# Vayu_i2c.net
KiCad netlist of a schematic drawn in EAGLE
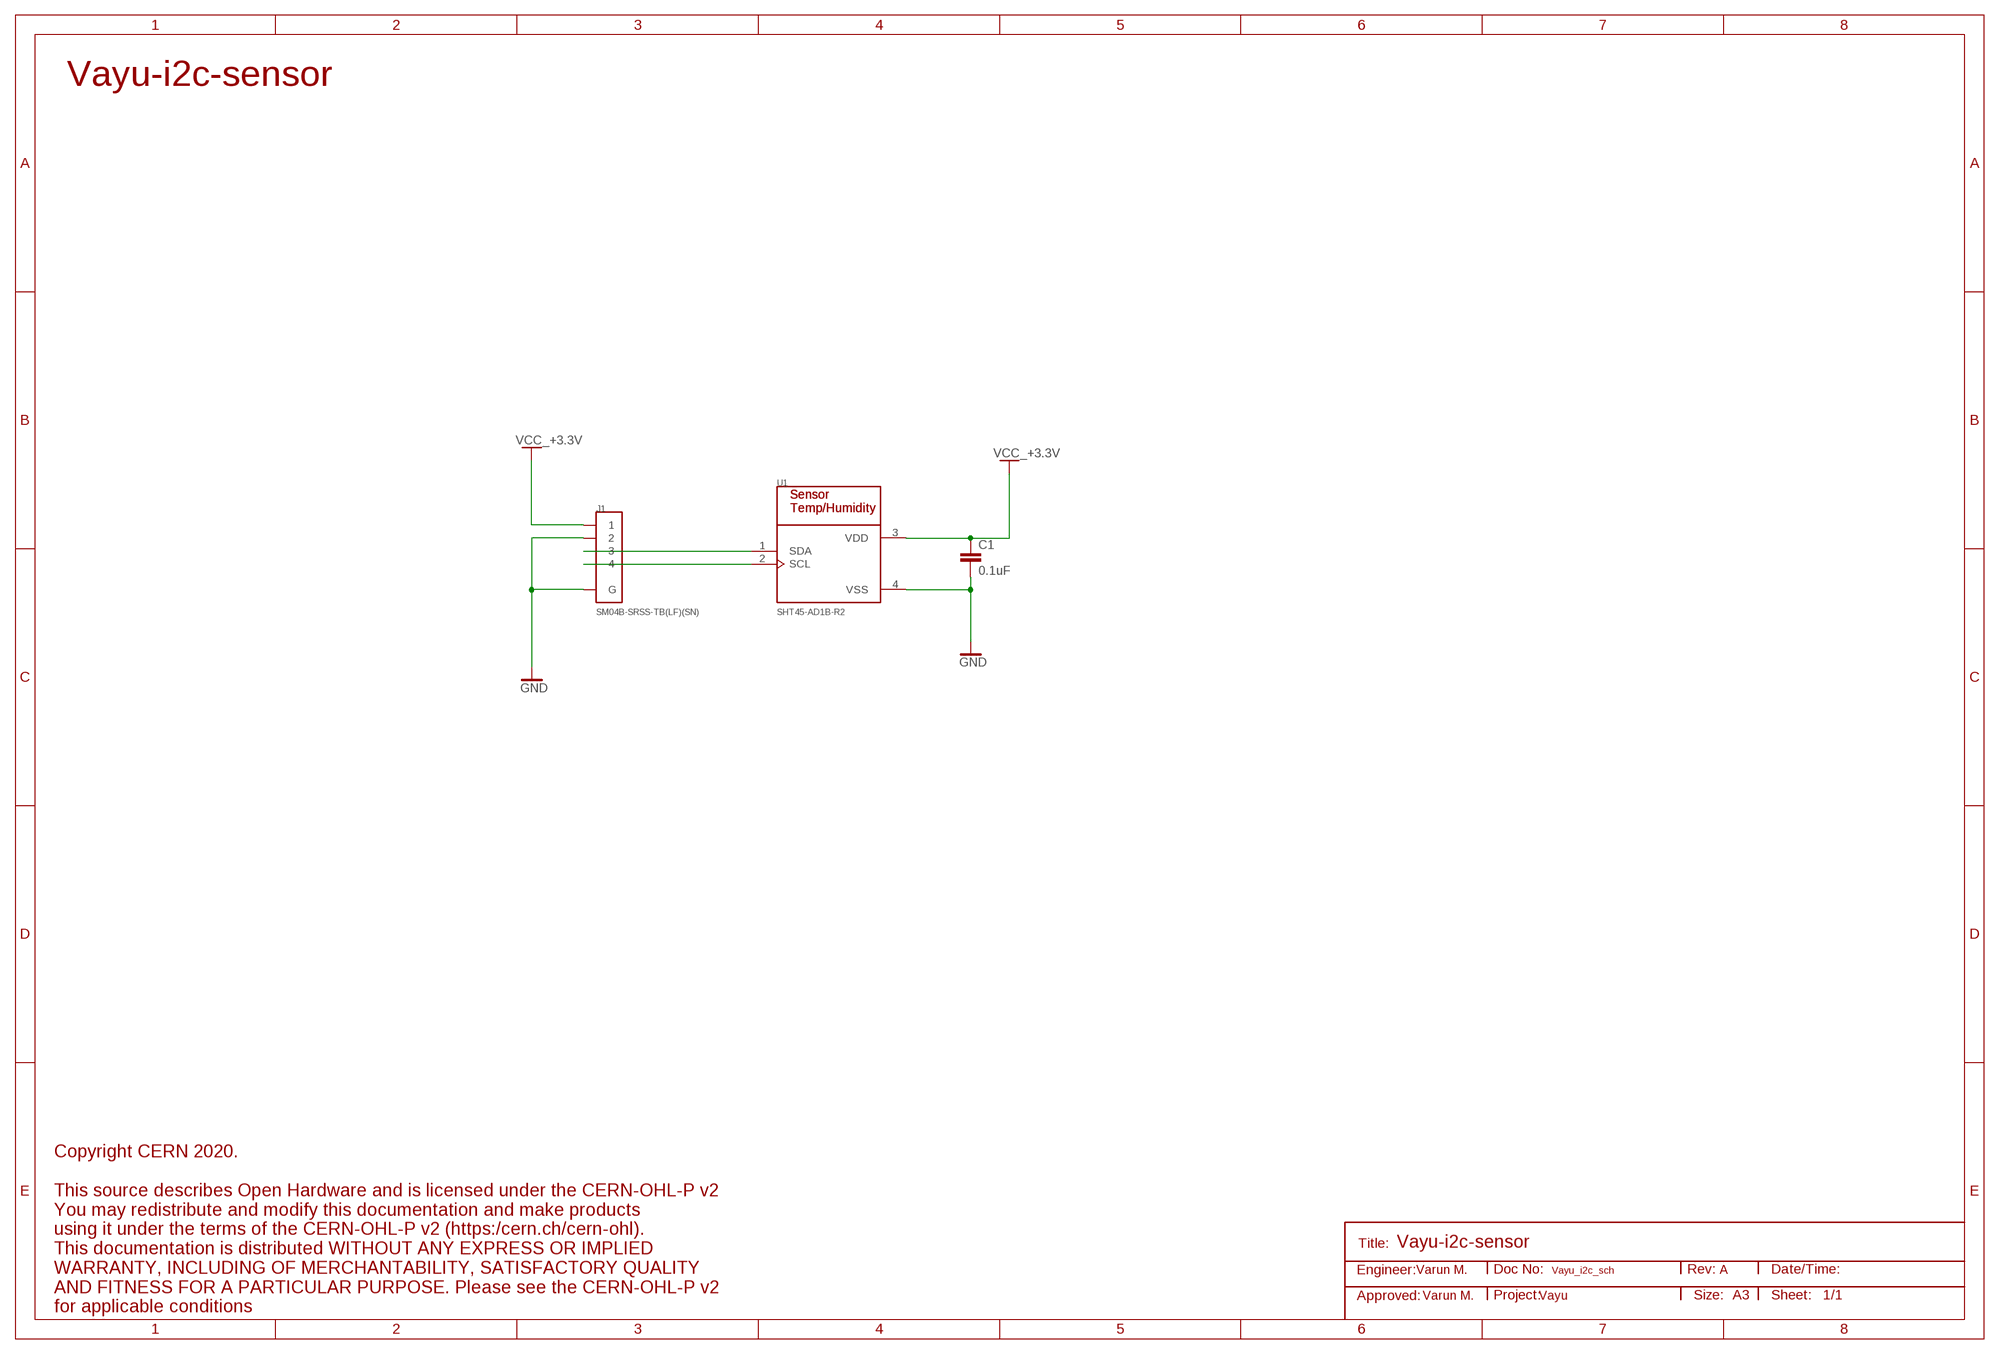
[diagram p0: schematic, sheet 1]

(export (version "E")
  (design (tool "Eeschema 10.0.6"))
  (components
    (comp (ref "C1")
      (value "0.1uF")
      (footprint "eagle-import:C0402")
      (libsource (lib "eagle-import") (part "C-EUC0402"))
    )
    (comp (ref "J1")
      (value "SM04B-SRSS-TB(LF)(SN)")
      (footprint "eagle-import:JST_SM04B-SRSS-TB(LF)(SN)")
      (fields (field (name "DIGI-KEY_PART_NUMBER") "455-1804-1-ND") (field (name "MF") "JST Sales"))
      (libsource (lib "eagle-import") (part "SM04B-SRSS-TB(LF)(SN)"))
    )
    (comp (ref "U1")
      (value "SHT45-AD1B-R2")
      (footprint "eagle-import:XDCR_SHT45-AD1B-R2")
      (libsource (lib "eagle-import") (part "SHT45-AD1B-R2"))
    )
  )
  (nets
    (net (code "1") (name "GND") (class "Default")
      (node (ref "C1") (pin "2") (pinfunction "2_2") (pintype "passive"))
      (node (ref "J1") (pin "2") (pinfunction "2_2") (pintype "passive"))
      (node (ref "J1") (pin "S1") (pinfunction "G_S1") (pintype "passive"))
      (node (ref "J1") (pin "S2") (pinfunction "G_S2") (pintype "passive"))
      (node (ref "U1") (pin "4") (pinfunction "VSS_4") (pintype "power_in"))
    )
    (net (code "2") (name "Net-(U1-SCL)") (class "Default")
      (node (ref "J1") (pin "4") (pinfunction "4_4") (pintype "passive"))
      (node (ref "U1") (pin "2") (pinfunction "SCL_2") (pintype "input"))
    )
    (net (code "3") (name "Net-(U1-SDA)") (class "Default")
      (node (ref "J1") (pin "3") (pinfunction "3_3") (pintype "passive"))
      (node (ref "U1") (pin "1") (pinfunction "SDA_1") (pintype "bidirectional"))
    )
    (net (code "4") (name "VCC_+3.3V") (class "Default")
      (node (ref "C1") (pin "1") (pinfunction "1_1") (pintype "passive"))
      (node (ref "J1") (pin "1") (pinfunction "1_1") (pintype "passive"))
      (node (ref "U1") (pin "3") (pinfunction "VDD_3") (pintype "power_in"))
    )
  )
)
